# flasher_without_opto.net
KiCad netlist of a schematic drawn in EAGLE
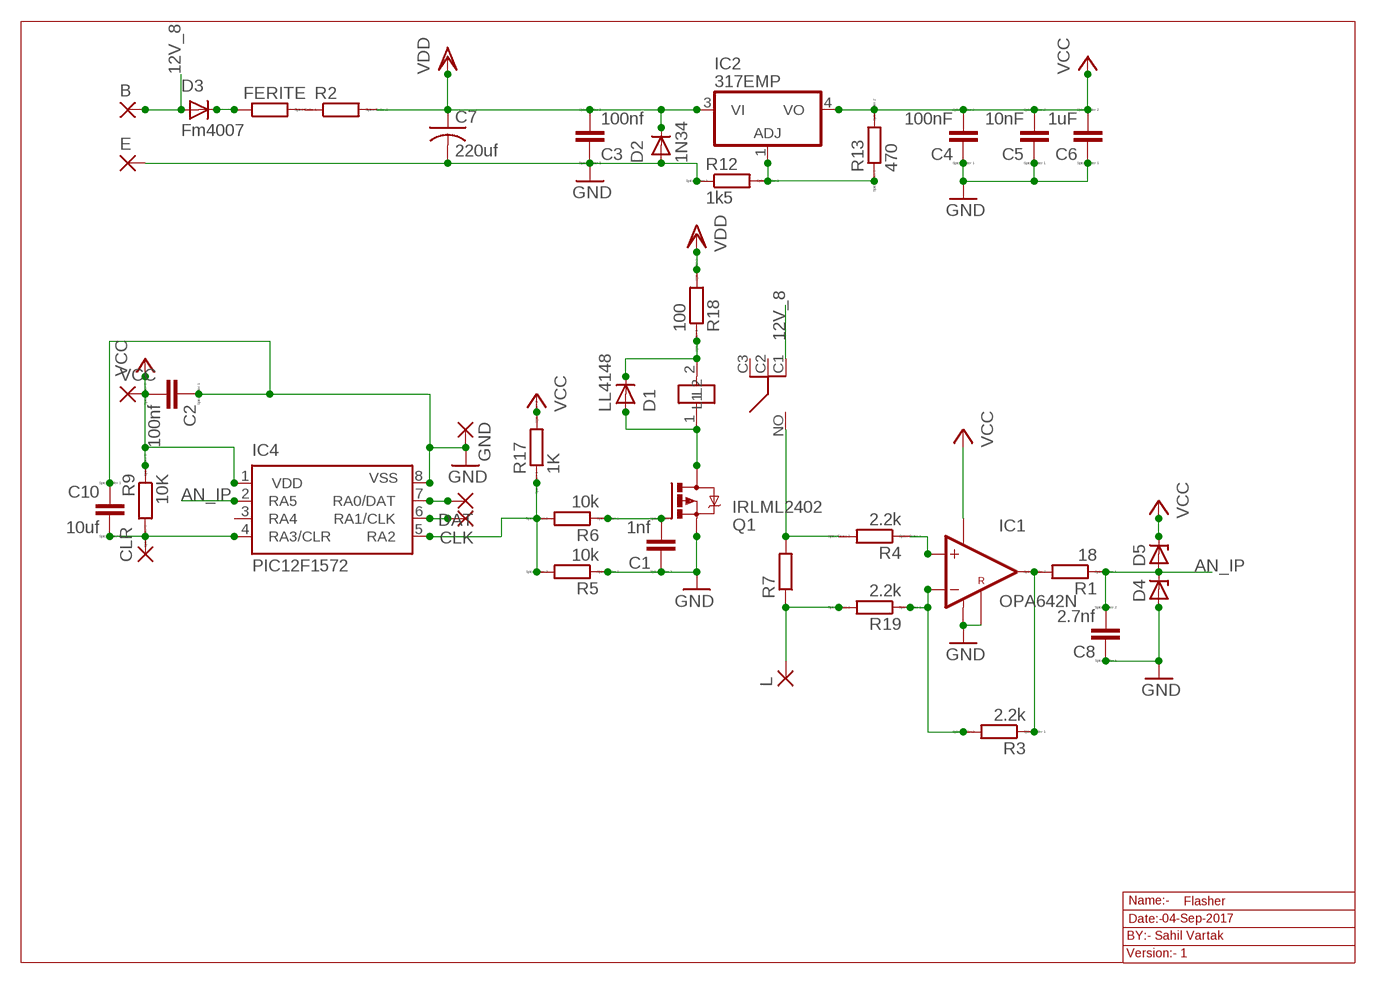
[diagram p0: schematic, sheet 1]

(export (version "E")
  (design (tool "Eeschema 10.0.6"))
  (components
    (comp (ref "B")
      (value "2,54/1,1")
      (footprint "eagle-import:2,54_1,1")
      (libsource (lib "eagle-import") (part "2,54/1,1"))
    )
    (comp (ref "C1")
      (value "1nf")
      (footprint "eagle-import:C0603")
      (libsource (lib "eagle-import") (part "CC0603"))
    )
    (comp (ref "C2")
      (value "100nf")
      (footprint "eagle-import:C0603")
      (libsource (lib "eagle-import") (part "CC0603"))
    )
    (comp (ref "C3")
      (value "100nf")
      (footprint "eagle-import:C0603")
      (libsource (lib "eagle-import") (part "CC0603"))
    )
    (comp (ref "C4")
      (value "100nF")
      (footprint "eagle-import:C0603")
      (libsource (lib "eagle-import") (part "CC0603"))
    )
    (comp (ref "C5")
      (value "10nF")
      (footprint "eagle-import:C0603")
      (libsource (lib "eagle-import") (part "CC0603"))
    )
    (comp (ref "C6")
      (value "1uF")
      (footprint "eagle-import:C0603")
      (libsource (lib "eagle-import") (part "CC0603"))
    )
    (comp (ref "C7")
      (value "220uf")
      (footprint "eagle-import:C025-025X050")
      (libsource (lib "eagle-import") (part "C-US025-025X050"))
    )
    (comp (ref "C8")
      (value "2.7nf")
      (footprint "eagle-import:C0603")
      (libsource (lib "eagle-import") (part "CC0603"))
    )
    (comp (ref "C10")
      (value "10uf")
      (footprint "eagle-import:C0603")
      (libsource (lib "eagle-import") (part "CC0603"))
    )
    (comp (ref "CLK")
      (value "1,6/0,8")
      (footprint "eagle-import:1,6_0,8")
      (libsource (lib "eagle-import") (part "1,6/0,8"))
    )
    (comp (ref "CLR")
      (value "1,6/0,8")
      (footprint "eagle-import:1,6_0,8")
      (libsource (lib "eagle-import") (part "1,6/0,8"))
    )
    (comp (ref "D1")
      (value "LL4148")
      (footprint "eagle-import:SMA-DO214AC")
      (libsource (lib "eagle-import") (part "GF1"))
    )
    (comp (ref "D2")
      (value "1N34")
      (footprint "eagle-import:SMA-DO214AC")
      (libsource (lib "eagle-import") (part "GF1"))
    )
    (comp (ref "D3")
      (value "Fm4007")
      (footprint "eagle-import:SMA-DO214AC")
      (libsource (lib "eagle-import") (part "GF1"))
    )
    (comp (ref "D4")
      (value "ZENER-DIODESOD80C")
      (footprint "eagle-import:SOD80C")
      (libsource (lib "eagle-import") (part "ZENER-DIODESOD80C"))
    )
    (comp (ref "D5")
      (value "ZENER-DIODESOD80C")
      (footprint "eagle-import:SOD80C")
      (libsource (lib "eagle-import") (part "ZENER-DIODESOD80C"))
    )
    (comp (ref "DAT")
      (value "1,6/0,8")
      (footprint "eagle-import:1,6_0,8")
      (libsource (lib "eagle-import") (part "1,6/0,8"))
    )
    (comp (ref "E")
      (value "2,54/1,1")
      (footprint "eagle-import:2,54_1,1")
      (libsource (lib "eagle-import") (part "2,54/1,1"))
    )
    (comp (ref "FERITE")
      (value "R-EU_R0603")
      (footprint "eagle-import:R0603")
      (libsource (lib "eagle-import") (part "R-EU_R0603"))
    )
    (comp (ref "GND")
      (value "1,6/0,8")
      (footprint "eagle-import:1,6_0,8")
      (libsource (lib "eagle-import") (part "1,6/0,8"))
    )
    (comp (ref "IC1")
      (value "OPA642N")
      (footprint "eagle-import:INA181")
      (libsource (lib "eagle-import") (part "OPA642N"))
    )
    (comp (ref "IC2")
      (value "317EMP")
      (footprint "eagle-import:SOT223")
      (libsource (lib "eagle-import") (part "317EMP"))
    )
    (comp (ref "IC4")
      (value "PIC12F1572")
      (footprint "eagle-import:SO-08")
      (fields (field (name "MF") "MICROCHIP") (field (name "MPN") "PIC12F675-E/SN"))
      (libsource (lib "eagle-import") (part "PIC12F6SN75"))
    )
    (comp (ref "K2")
      (value "RL703")
      (footprint "eagle-import:RL703")
      (libsource (lib "eagle-import") (part "RL703"))
    )
    (comp (ref "L")
      (value "2,54/1,1")
      (footprint "eagle-import:2,54_1,1")
      (libsource (lib "eagle-import") (part "2,54/1,1"))
    )
    (comp (ref "Q1")
      (value "IRLML2402")
      (footprint "eagle-import:MICRO3")
      (libsource (lib "eagle-import") (part "IRLML5203"))
    )
    (comp (ref "R1")
      (value "18")
      (footprint "eagle-import:R0603")
      (libsource (lib "eagle-import") (part "RR0603"))
    )
    (comp (ref "R2")
      (value "RR5025")
      (footprint "eagle-import:R5025")
      (libsource (lib "eagle-import") (part "RR5025"))
    )
    (comp (ref "R3")
      (value "2.2k")
      (footprint "eagle-import:R0603")
      (libsource (lib "eagle-import") (part "RR0603"))
    )
    (comp (ref "R4")
      (value "2.2k")
      (footprint "eagle-import:R0603")
      (libsource (lib "eagle-import") (part "RR0603"))
    )
    (comp (ref "R5")
      (value "10k")
      (footprint "eagle-import:R0603")
      (libsource (lib "eagle-import") (part "RR0603"))
    )
    (comp (ref "R6")
      (value "10k")
      (footprint "eagle-import:R0603")
      (libsource (lib "eagle-import") (part "RR0603"))
    )
    (comp (ref "R7")
      (value "R-EU_0207/15")
      (footprint "eagle-import:0207_15")
      (libsource (lib "eagle-import") (part "R-EU_0207/15"))
    )
    (comp (ref "R9")
      (value "10K")
      (footprint "eagle-import:R0603")
      (libsource (lib "eagle-import") (part "RR0603"))
    )
    (comp (ref "R12")
      (value "1k5")
      (footprint "eagle-import:R0603")
      (libsource (lib "eagle-import") (part "RR0603"))
    )
    (comp (ref "R13")
      (value "470")
      (footprint "eagle-import:R0603")
      (libsource (lib "eagle-import") (part "RR0603"))
    )
    (comp (ref "R17")
      (value "1K")
      (footprint "eagle-import:R0603")
      (libsource (lib "eagle-import") (part "RR0603"))
    )
    (comp (ref "R18")
      (value "100")
      (footprint "eagle-import:R0603")
      (libsource (lib "eagle-import") (part "RR0603"))
    )
    (comp (ref "R19")
      (value "2.2k")
      (footprint "eagle-import:R0603")
      (libsource (lib "eagle-import") (part "RR0603"))
    )
    (comp (ref "VCC")
      (value "1,6/0,8")
      (footprint "eagle-import:1,6_0,8")
      (libsource (lib "eagle-import") (part "1,6/0,8"))
    )
  )
  (nets
    (net (code "1") (name "/12V_8") (class "Default")
      (node (ref "B") (pin "1") (pinfunction "P_1") (pintype "passive"))
      (node (ref "D3") (pin "A") (pinfunction "A_A") (pintype "passive"))
      (node (ref "K2") (pin "C1") (pinfunction "C1_C1") (pintype "bidirectional"))
    )
    (net (code "2") (name "/AN_IP") (class "Default")
      (node (ref "C8") (pin "2") (pinfunction "2_2") (pintype "passive"))
      (node (ref "D4") (pin "C") (pinfunction "C_C") (pintype "passive"))
      (node (ref "D5") (pin "A") (pinfunction "A_A") (pintype "passive"))
      (node (ref "IC4") (pin "2") (pinfunction "RA5_2") (pintype "bidirectional"))
      (node (ref "R1") (pin "1") (pinfunction "1_1") (pintype "passive"))
    )
    (net (code "3") (name "GND") (class "Default")
      (node (ref "C1") (pin "1") (pinfunction "1_1") (pintype "passive"))
      (node (ref "C10") (pin "1") (pinfunction "1_1") (pintype "passive"))
      (node (ref "C2") (pin "1") (pinfunction "1_1") (pintype "passive"))
      (node (ref "C3") (pin "1") (pinfunction "1_1") (pintype "passive"))
      (node (ref "C4") (pin "1") (pinfunction "1_1") (pintype "passive"))
      (node (ref "C5") (pin "1") (pinfunction "1_1") (pintype "passive"))
      (node (ref "C6") (pin "1") (pinfunction "1_1") (pintype "passive"))
      (node (ref "C7") (pin "2") (pinfunction "2_2") (pintype "passive"))
      (node (ref "C8") (pin "1") (pinfunction "1_1") (pintype "passive"))
      (node (ref "D2") (pin "A") (pinfunction "A_A") (pintype "passive"))
      (node (ref "D4") (pin "A") (pinfunction "A_A") (pintype "passive"))
      (node (ref "E") (pin "1") (pinfunction "P_1") (pintype "passive"))
      (node (ref "GND") (pin "1") (pinfunction "P_1") (pintype "passive"))
      (node (ref "IC1") (pin "P$2") (pinfunction "V-_P$2") (pintype "power_in"))
      (node (ref "IC1") (pin "P$5") (pinfunction "REF_P$5") (pintype "bidirectional"))
      (node (ref "IC4") (pin "8") (pinfunction "VSS_8") (pintype "power_in"))
      (node (ref "Q1") (pin "2") (pinfunction "S_2") (pintype "passive"))
      (node (ref "R12") (pin "1") (pinfunction "1_1") (pintype "passive"))
      (node (ref "R5") (pin "1") (pinfunction "1_1") (pintype "passive"))
    )
    (net (code "4") (name "Net-(CLK-P)") (class "Default")
      (node (ref "CLK") (pin "1") (pinfunction "P_1") (pintype "passive"))
      (node (ref "IC4") (pin "6") (pinfunction "RA1/CLK_6") (pintype "bidirectional"))
    )
    (net (code "5") (name "Net-(CLR-P)") (class "Default")
      (node (ref "C10") (pin "2") (pinfunction "2_2") (pintype "passive"))
      (node (ref "CLR") (pin "1") (pinfunction "P_1") (pintype "passive"))
      (node (ref "IC4") (pin "4") (pinfunction "RA3/CLR_4") (pintype "input"))
      (node (ref "R9") (pin "2") (pinfunction "2_2") (pintype "passive"))
    )
    (net (code "6") (name "Net-(D1-C)") (class "Default")
      (node (ref "D1") (pin "K") (pinfunction "C_K") (pintype "passive"))
      (node (ref "K2") (pin "2") (pinfunction "L1_2") (pintype "bidirectional"))
      (node (ref "R18") (pin "1") (pinfunction "1_1") (pintype "passive"))
    )
    (net (code "7") (name "Net-(D3-C)") (class "Default")
      (node (ref "D3") (pin "K") (pinfunction "C_K") (pintype "passive"))
      (node (ref "FERITE") (pin "1") (pinfunction "1_1") (pintype "passive"))
    )
    (net (code "8") (name "Net-(DAT-P)") (class "Default")
      (node (ref "DAT") (pin "1") (pinfunction "P_1") (pintype "passive"))
      (node (ref "IC4") (pin "7") (pinfunction "RA0/DAT_7") (pintype "bidirectional"))
    )
    (net (code "9") (name "Net-(FERITE-Pad2)") (class "Default")
      (node (ref "FERITE") (pin "2") (pinfunction "2_2") (pintype "passive"))
      (node (ref "R2") (pin "1") (pinfunction "1_1") (pintype "passive"))
    )
    (net (code "10") (name "Net-(IC1-+IN)") (class "Default")
      (node (ref "IC1") (pin "P$3") (pinfunction "+IN_P$3") (pintype "input"))
      (node (ref "R4") (pin "1") (pinfunction "1_1") (pintype "passive"))
    )
    (net (code "11") (name "Net-(IC1--IN)") (class "Default")
      (node (ref "IC1") (pin "P$4") (pinfunction "-IN_P$4") (pintype "input"))
      (node (ref "R19") (pin "1") (pinfunction "1_1") (pintype "passive"))
      (node (ref "R3") (pin "2") (pinfunction "2_2") (pintype "passive"))
    )
    (net (code "12") (name "Net-(IC1-OUT)") (class "Default")
      (node (ref "IC1") (pin "P$1") (pinfunction "OUT_P$1") (pintype "output"))
      (node (ref "R1") (pin "2") (pinfunction "2_2") (pintype "passive"))
      (node (ref "R3") (pin "1") (pinfunction "1_1") (pintype "passive"))
    )
    (net (code "13") (name "Net-(IC2-ADJ)") (class "Default")
      (node (ref "IC2") (pin "1") (pinfunction "ADJ_1") (pintype "input"))
      (node (ref "R12") (pin "2") (pinfunction "2_2") (pintype "passive"))
      (node (ref "R13") (pin "1") (pinfunction "1_1") (pintype "passive"))
    )
    (net (code "14") (name "Net-(IC4-RA2)") (class "Default")
      (node (ref "IC4") (pin "5") (pinfunction "RA2_5") (pintype "bidirectional"))
      (node (ref "R17") (pin "1") (pinfunction "1_1") (pintype "passive"))
      (node (ref "R5") (pin "2") (pinfunction "2_2") (pintype "passive"))
      (node (ref "R6") (pin "2") (pinfunction "2_2") (pintype "passive"))
    )
    (net (code "15") (name "Net-(K2-L2)") (class "Default")
      (node (ref "D1") (pin "A") (pinfunction "A_A") (pintype "passive"))
      (node (ref "K2") (pin "1") (pinfunction "L2_1") (pintype "bidirectional"))
      (node (ref "Q1") (pin "3") (pinfunction "D_3") (pintype "passive"))
    )
    (net (code "16") (name "Net-(K2-PadNO)") (class "Default")
      (node (ref "K2") (pin "NO") (pinfunction "NO_NO") (pintype "bidirectional"))
      (node (ref "R4") (pin "2") (pinfunction "2_2") (pintype "passive"))
      (node (ref "R7") (pin "2") (pinfunction "2_2") (pintype "passive"))
    )
    (net (code "17") (name "Net-(L-P)") (class "Default")
      (node (ref "L") (pin "1") (pinfunction "P_1") (pintype "passive"))
      (node (ref "R19") (pin "2") (pinfunction "2_2") (pintype "passive"))
      (node (ref "R7") (pin "1") (pinfunction "1_1") (pintype "passive"))
    )
    (net (code "18") (name "Net-(Q1-G)") (class "Default")
      (node (ref "C1") (pin "2") (pinfunction "2_2") (pintype "passive"))
      (node (ref "Q1") (pin "1") (pinfunction "G_1") (pintype "passive"))
      (node (ref "R6") (pin "1") (pinfunction "1_1") (pintype "passive"))
    )
    (net (code "19") (name "VCC") (class "Default")
      (node (ref "C2") (pin "2") (pinfunction "2_2") (pintype "passive"))
      (node (ref "C4") (pin "2") (pinfunction "2_2") (pintype "passive"))
      (node (ref "C5") (pin "2") (pinfunction "2_2") (pintype "passive"))
      (node (ref "C6") (pin "2") (pinfunction "2_2") (pintype "passive"))
      (node (ref "D5") (pin "C") (pinfunction "C_C") (pintype "passive"))
      (node (ref "IC1") (pin "P$6") (pinfunction "V+_P$6") (pintype "power_in"))
      (node (ref "IC2") (pin "4") (pinfunction "VO_4") (pintype "passive"))
      (node (ref "IC4") (pin "1") (pinfunction "VDD_1") (pintype "power_in"))
      (node (ref "R13") (pin "2") (pinfunction "2_2") (pintype "passive"))
      (node (ref "R17") (pin "2") (pinfunction "2_2") (pintype "passive"))
      (node (ref "R9") (pin "1") (pinfunction "1_1") (pintype "passive"))
      (node (ref "VCC") (pin "1") (pinfunction "P_1") (pintype "passive"))
    )
    (net (code "20") (name "VDD") (class "Default")
      (node (ref "C3") (pin "2") (pinfunction "2_2") (pintype "passive"))
      (node (ref "C7") (pin "1") (pinfunction "1_1") (pintype "passive"))
      (node (ref "D2") (pin "K") (pinfunction "C_K") (pintype "passive"))
      (node (ref "IC2") (pin "3") (pinfunction "VI_3") (pintype "input"))
      (node (ref "R18") (pin "2") (pinfunction "2_2") (pintype "passive"))
      (node (ref "R2") (pin "2") (pinfunction "2_2") (pintype "passive"))
    )
    (net (code "21") (name "unconnected-(IC4-RA4-Pad3)") (class "Default")
      (node (ref "IC4") (pin "3") (pinfunction "RA4_3") (pintype "bidirectional"))
    )
    (net (code "22") (name "unconnected-(K2-PadC2)") (class "Default")
      (node (ref "K2") (pin "C2") (pinfunction "C2_C2") (pintype "bidirectional"))
    )
    (net (code "23") (name "unconnected-(K2-PadC3)") (class "Default")
      (node (ref "K2") (pin "C3") (pinfunction "C3_C3") (pintype "bidirectional"))
    )
  )
)
